# Motor_Driver_v4.net
KiCad netlist of a schematic drawn in EAGLE
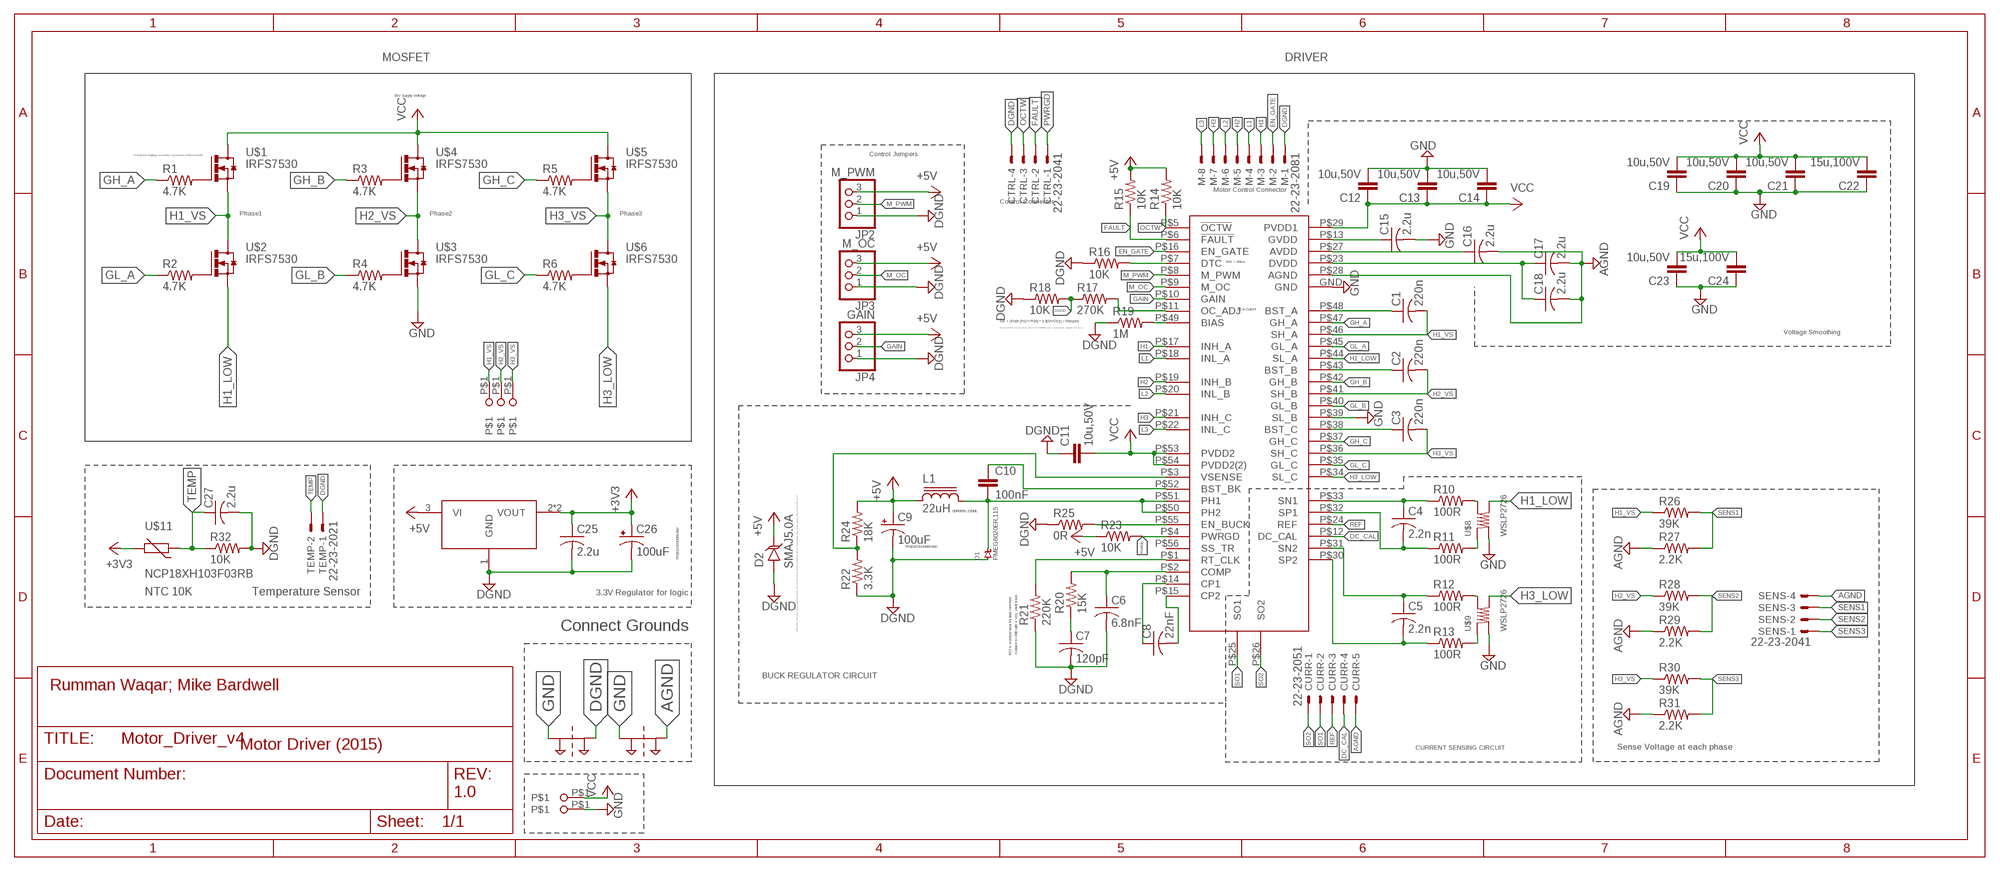
[diagram p0: schematic, sheet 1]

(export (version "E")
  (design (tool "Eeschema 10.0.6"))
  (components
    (comp (ref "C1")
      (value "220n")
      (footprint "eagle-import:C0805")
      (libsource (lib "eagle-import") (part "C-USC0805"))
    )
    (comp (ref "C2")
      (value "220n")
      (footprint "eagle-import:C0805")
      (libsource (lib "eagle-import") (part "C-USC0805"))
    )
    (comp (ref "C3")
      (value "220n")
      (footprint "eagle-import:C0805")
      (libsource (lib "eagle-import") (part "C-USC0805"))
    )
    (comp (ref "C4")
      (value "2.2n")
      (footprint "eagle-import:C0603")
      (libsource (lib "eagle-import") (part "C-USC0603"))
    )
    (comp (ref "C5")
      (value "2.2n")
      (footprint "eagle-import:C0603")
      (libsource (lib "eagle-import") (part "C-USC0603"))
    )
    (comp (ref "C6")
      (value "6.8nF")
      (footprint "eagle-import:C0603")
      (libsource (lib "eagle-import") (part "C-USC0603"))
    )
    (comp (ref "C7")
      (value "120pF")
      (footprint "eagle-import:C0603")
      (libsource (lib "eagle-import") (part "C-USC0603"))
    )
    (comp (ref "C8")
      (value "22nF")
      (footprint "eagle-import:C0603")
      (libsource (lib "eagle-import") (part "C-USC0603"))
    )
    (comp (ref "C9")
      (value "100uF")
      (footprint "eagle-import:EIA3528-KIT")
      (libsource (lib "eagle-import") (part "CAP_POL3528-KIT"))
    )
    (comp (ref "C10")
      (value "100nF")
      (footprint "eagle-import:0805")
      (libsource (lib "eagle-import") (part "CAP0805"))
    )
    (comp (ref "C11")
      (value "10u,50V")
      (footprint "eagle-import:1206")
      (libsource (lib "eagle-import") (part "CAP1206"))
    )
    (comp (ref "C12")
      (value "10u,50V")
      (footprint "eagle-import:1206")
      (libsource (lib "eagle-import") (part "CAP1206"))
    )
    (comp (ref "C13")
      (value "10u,50V")
      (footprint "eagle-import:1206")
      (libsource (lib "eagle-import") (part "CAP1206"))
    )
    (comp (ref "C14")
      (value "10u,50V")
      (footprint "eagle-import:1206")
      (libsource (lib "eagle-import") (part "CAP1206"))
    )
    (comp (ref "C15")
      (value "2.2u")
      (footprint "eagle-import:C0805")
      (libsource (lib "eagle-import") (part "C-USC0805"))
    )
    (comp (ref "C16")
      (value "2.2u")
      (footprint "eagle-import:C0805")
      (libsource (lib "eagle-import") (part "C-USC0805"))
    )
    (comp (ref "C17")
      (value "2.2u")
      (footprint "eagle-import:C0805")
      (libsource (lib "eagle-import") (part "C-USC0805"))
    )
    (comp (ref "C18")
      (value "2.2u")
      (footprint "eagle-import:C0805")
      (libsource (lib "eagle-import") (part "C-USC0805"))
    )
    (comp (ref "C19")
      (value "10u,50V")
      (footprint "eagle-import:1206")
      (libsource (lib "eagle-import") (part "CAP1206"))
    )
    (comp (ref "C20")
      (value "10u,50V")
      (footprint "eagle-import:1206")
      (libsource (lib "eagle-import") (part "CAP1206"))
    )
    (comp (ref "C21")
      (value "10u,50V")
      (footprint "eagle-import:1206")
      (libsource (lib "eagle-import") (part "CAP1206"))
    )
    (comp (ref "C22")
      (value "15u,100V")
      (footprint "eagle-import:C2220K")
      (libsource (lib "eagle-import") (part "C-EUC2220K"))
    )
    (comp (ref "C23")
      (value "10u,50V")
      (footprint "eagle-import:1206")
      (libsource (lib "eagle-import") (part "CAP1206"))
    )
    (comp (ref "C24")
      (value "15u,100V")
      (footprint "eagle-import:C2220K")
      (libsource (lib "eagle-import") (part "C-EUC2220K"))
    )
    (comp (ref "C25")
      (value "2.2u")
      (footprint "eagle-import:C0805")
      (libsource (lib "eagle-import") (part "C-USC0805"))
    )
    (comp (ref "C26")
      (value "100uF")
      (footprint "eagle-import:EIA3528-KIT")
      (libsource (lib "eagle-import") (part "CAP_POL3528-KIT"))
    )
    (comp (ref "C27")
      (value "2.2u")
      (footprint "eagle-import:C0805")
      (libsource (lib "eagle-import") (part "C-USC0805"))
    )
    (comp (ref "CTRL")
      (value "22-23-2041")
      (footprint "eagle-import:22-23-2041")
      (fields (field (name "MF") "MOLEX"))
      (libsource (lib "eagle-import") (part "22-23-2041"))
    )
    (comp (ref "CURR")
      (value "22-23-2051")
      (footprint "eagle-import:22-23-2051")
      (fields (field (name "MF") "MOLEX"))
      (libsource (lib "eagle-import") (part "22-23-2051"))
    )
    (comp (ref "D1")
      (value "PMEG6020ER,115")
      (footprint "eagle-import:SOD123W")
      (libsource (lib "eagle-import") (part "DIODE[SCHOTKY]-SOD123W"))
    )
    (comp (ref "D2")
      (value "SMAJ5.0A")
      (footprint "eagle-import:SMA-DIODE")
      (libsource (lib "eagle-import") (part "TVSSMA"))
    )
    (comp (ref "JP2")
      (value "M_PWM")
      (footprint "eagle-import:1X03")
      (libsource (lib "eagle-import") (part "PINHD-1X3"))
    )
    (comp (ref "JP3")
      (value "M_OC")
      (footprint "eagle-import:1X03")
      (libsource (lib "eagle-import") (part "PINHD-1X3"))
    )
    (comp (ref "JP4")
      (value "GAIN")
      (footprint "eagle-import:1X03")
      (libsource (lib "eagle-import") (part "PINHD-1X3"))
    )
    (comp (ref "L1")
      (value "22uH")
      (footprint "eagle-import:SDR0805")
      (libsource (lib "eagle-import") (part "SDR0805"))
    )
    (comp (ref "M")
      (value "22-23-2081")
      (footprint "eagle-import:22-23-2081")
      (fields (field (name "MF") "MOLEX"))
      (libsource (lib "eagle-import") (part "22-23-2081"))
    )
    (comp (ref "PT1")
      (value "2PT_GND_TIE")
      (footprint "eagle-import:2PT_GND_TIE")
      (libsource (lib "eagle-import") (part "2PT_GND_TIE"))
    )
    (comp (ref "PT2")
      (value "2PT_GND_TIE")
      (footprint "eagle-import:2PT_GND_TIE")
      (libsource (lib "eagle-import") (part "2PT_GND_TIE"))
    )
    (comp (ref "R1")
      (value "4.7K")
      (footprint "eagle-import:R0603")
      (libsource (lib "eagle-import") (part "R-US_R0603"))
    )
    (comp (ref "R2")
      (value "4.7K")
      (footprint "eagle-import:R0603")
      (libsource (lib "eagle-import") (part "R-US_R0603"))
    )
    (comp (ref "R3")
      (value "4.7K")
      (footprint "eagle-import:R0603")
      (libsource (lib "eagle-import") (part "R-US_R0603"))
    )
    (comp (ref "R4")
      (value "4.7K")
      (footprint "eagle-import:R0603")
      (libsource (lib "eagle-import") (part "R-US_R0603"))
    )
    (comp (ref "R5")
      (value "4.7K")
      (footprint "eagle-import:R0603")
      (libsource (lib "eagle-import") (part "R-US_R0603"))
    )
    (comp (ref "R6")
      (value "4.7K")
      (footprint "eagle-import:R0603")
      (libsource (lib "eagle-import") (part "R-US_R0603"))
    )
    (comp (ref "R10")
      (value "100R")
      (footprint "eagle-import:R0603")
      (libsource (lib "eagle-import") (part "R-US_R0603"))
    )
    (comp (ref "R11")
      (value "100R")
      (footprint "eagle-import:R0603")
      (libsource (lib "eagle-import") (part "R-US_R0603"))
    )
    (comp (ref "R12")
      (value "100R")
      (footprint "eagle-import:R0603")
      (libsource (lib "eagle-import") (part "R-US_R0603"))
    )
    (comp (ref "R13")
      (value "100R")
      (footprint "eagle-import:R0603")
      (libsource (lib "eagle-import") (part "R-US_R0603"))
    )
    (comp (ref "R14")
      (value "10K")
      (footprint "eagle-import:R0603")
      (libsource (lib "eagle-import") (part "R-US_R0603"))
    )
    (comp (ref "R15")
      (value "10K")
      (footprint "eagle-import:R0603")
      (libsource (lib "eagle-import") (part "R-US_R0603"))
    )
    (comp (ref "R16")
      (value "10K")
      (footprint "eagle-import:R0603")
      (libsource (lib "eagle-import") (part "R-US_R0603"))
    )
    (comp (ref "R17")
      (value "270K")
      (footprint "eagle-import:R0603")
      (libsource (lib "eagle-import") (part "R-US_R0603"))
    )
    (comp (ref "R18")
      (value "10K")
      (footprint "eagle-import:R0603")
      (libsource (lib "eagle-import") (part "R-US_R0603"))
    )
    (comp (ref "R19")
      (value "1M")
      (footprint "eagle-import:R0603")
      (libsource (lib "eagle-import") (part "R-US_R0603"))
    )
    (comp (ref "R20")
      (value "15K")
      (footprint "eagle-import:R0603")
      (libsource (lib "eagle-import") (part "R-US_R0603"))
    )
    (comp (ref "R21")
      (value "220K")
      (footprint "eagle-import:R0603")
      (libsource (lib "eagle-import") (part "R-US_R0603"))
    )
    (comp (ref "R22")
      (value "3.3K")
      (footprint "eagle-import:R0603")
      (libsource (lib "eagle-import") (part "R-US_R0603"))
    )
    (comp (ref "R23")
      (value "10K")
      (footprint "eagle-import:R0603")
      (libsource (lib "eagle-import") (part "R-US_R0603"))
    )
    (comp (ref "R24")
      (value "18K")
      (footprint "eagle-import:R0603")
      (libsource (lib "eagle-import") (part "R-US_R0603"))
    )
    (comp (ref "R25")
      (value "0R")
      (footprint "eagle-import:R0603")
      (libsource (lib "eagle-import") (part "R-US_R0603"))
    )
    (comp (ref "R26")
      (value "39K")
      (footprint "eagle-import:R0805")
      (libsource (lib "eagle-import") (part "R-US_R0805"))
    )
    (comp (ref "R27")
      (value "2.2K")
      (footprint "eagle-import:R0805")
      (libsource (lib "eagle-import") (part "R-US_R0805"))
    )
    (comp (ref "R28")
      (value "39K")
      (footprint "eagle-import:R0805")
      (libsource (lib "eagle-import") (part "R-US_R0805"))
    )
    (comp (ref "R29")
      (value "2.2K")
      (footprint "eagle-import:R0805")
      (libsource (lib "eagle-import") (part "R-US_R0805"))
    )
    (comp (ref "R30")
      (value "39K")
      (footprint "eagle-import:R0805")
      (libsource (lib "eagle-import") (part "R-US_R0805"))
    )
    (comp (ref "R31")
      (value "2.2K")
      (footprint "eagle-import:R0805")
      (libsource (lib "eagle-import") (part "R-US_R0805"))
    )
    (comp (ref "R32")
      (value "10K")
      (footprint "eagle-import:M0805")
      (libsource (lib "eagle-import") (part "R-US_M0805"))
    )
    (comp (ref "SENS")
      (value "22-23-2041")
      (footprint "eagle-import:22-23-2041")
      (fields (field (name "MF") "MOLEX"))
      (libsource (lib "eagle-import") (part "22-23-2041"))
    )
    (comp (ref "TEMP")
      (value "22-23-2021")
      (footprint "eagle-import:22-23-2021")
      (fields (field (name "MF") "MOLEX"))
      (libsource (lib "eagle-import") (part "22-23-2021"))
    )
    (comp (ref "U$1")
      (value "IRFS7530")
      (footprint "eagle-import:IRF7530_HEATSINK")
      (libsource (lib "eagle-import") (part "IRFS7530_HEATSINK"))
    )
    (comp (ref "U$2")
      (value "IRFS7530")
      (footprint "eagle-import:IRF7530_HEATSINK")
      (libsource (lib "eagle-import") (part "IRFS7530_HEATSINK"))
    )
    (comp (ref "U$3")
      (value "IRFS7530")
      (footprint "eagle-import:IRF7530_HEATSINK")
      (libsource (lib "eagle-import") (part "IRFS7530_HEATSINK"))
    )
    (comp (ref "U$4")
      (value "IRFS7530")
      (footprint "eagle-import:IRF7530_HEATSINK")
      (libsource (lib "eagle-import") (part "IRFS7530_HEATSINK"))
    )
    (comp (ref "U$5")
      (value "IRFS7530")
      (footprint "eagle-import:IRF7530_HEATSINK")
      (libsource (lib "eagle-import") (part "IRFS7530_HEATSINK"))
    )
    (comp (ref "U$6")
      (value "IRFS7530")
      (footprint "eagle-import:IRF7530_HEATSINK")
      (libsource (lib "eagle-import") (part "IRFS7530_HEATSINK"))
    )
    (comp (ref "U$7")
      (value "DRV8302")
      (footprint "eagle-import:DRV8302")
      (libsource (lib "eagle-import") (part "DRV8302"))
    )
    (comp (ref "U$8")
      (value "WSLP2726")
      (footprint "eagle-import:WSLP2726")
      (libsource (lib "eagle-import") (part "WSLP2726"))
    )
    (comp (ref "U$9")
      (value "WSLP2726")
      (footprint "eagle-import:WSLP2726")
      (libsource (lib "eagle-import") (part "WSLP2726"))
    )
    (comp (ref "U$10")
      (value "TC2117")
      (footprint "eagle-import:SOT223")
      (libsource (lib "eagle-import") (part "TC2117"))
    )
    (comp (ref "U$11")
      (value "NCP18XH103F03RB")
      (footprint "eagle-import:R0603")
      (libsource (lib "eagle-import") (part "NCP18XH103F03RB"))
    )
    (comp (ref "U$12")
      (value "1CONN_SOLDER")
      (footprint "eagle-import:1CONN_PAD")
      (libsource (lib "eagle-import") (part "1CONN_SOLDER"))
    )
    (comp (ref "U$13")
      (value "1CONN_SOLDER")
      (footprint "eagle-import:1CONN_PAD")
      (libsource (lib "eagle-import") (part "1CONN_SOLDER"))
    )
    (comp (ref "U$14")
      (value "1CONN_SOLDER")
      (footprint "eagle-import:1CONN_PAD")
      (libsource (lib "eagle-import") (part "1CONN_SOLDER"))
    )
    (comp (ref "U$15")
      (value "1CONN_SOLDER")
      (footprint "eagle-import:1CONN_PAD")
      (libsource (lib "eagle-import") (part "1CONN_SOLDER"))
    )
    (comp (ref "U$16")
      (value "1CONN_SOLDER")
      (footprint "eagle-import:1CONN_PAD")
      (libsource (lib "eagle-import") (part "1CONN_SOLDER"))
    )
  )
  (nets
    (net (code "1") (name "+3V3") (class "Default")
      (node (ref "C25") (pin "1") (pinfunction "1_1") (pintype "passive"))
      (node (ref "C26") (pin "A") (pinfunction "+_A") (pintype "passive"))
      (node (ref "U$10") (pin "2") (pinfunction "VOUT_2") (pintype "bidirectional"))
      (node (ref "U$10") (pin "4") (pinfunction "VOUT_4") (pintype "bidirectional"))
      (node (ref "U$11") (pin "2") (pinfunction "2_2") (pintype "passive"))
    )
    (net (code "2") (name "+5V") (class "Default")
      (node (ref "C9") (pin "A") (pinfunction "+_A") (pintype "passive"))
      (node (ref "D2") (pin "C") (pinfunction "C_C") (pintype "passive"))
      (node (ref "JP2") (pin "3") (pinfunction "3_3") (pintype "passive"))
      (node (ref "JP3") (pin "3") (pinfunction "3_3") (pintype "passive"))
      (node (ref "JP4") (pin "3") (pinfunction "3_3") (pintype "passive"))
      (node (ref "L1") (pin "1") (pinfunction "1_1") (pintype "passive"))
      (node (ref "R14") (pin "2") (pinfunction "2_2") (pintype "passive"))
      (node (ref "R15") (pin "2") (pinfunction "2_2") (pintype "passive"))
      (node (ref "R23") (pin "1") (pinfunction "1_1") (pintype "passive"))
      (node (ref "R24") (pin "2") (pinfunction "2_2") (pintype "passive"))
      (node (ref "U$10") (pin "3") (pinfunction "VI_3") (pintype "bidirectional"))
    )
    (net (code "3") (name "AGND") (class "Default")
      (node (ref "C16") (pin "2") (pinfunction "2_2") (pintype "passive"))
      (node (ref "C17") (pin "2") (pinfunction "2_2") (pintype "passive"))
      (node (ref "C18") (pin "2") (pinfunction "2_2") (pintype "passive"))
      (node (ref "CURR") (pin "5") (pinfunction "S_5") (pintype "passive"))
      (node (ref "PT2") (pin "P$2") (pinfunction "P$2_P$2") (pintype "bidirectional"))
      (node (ref "R27") (pin "1") (pinfunction "1_1") (pintype "passive"))
      (node (ref "R29") (pin "1") (pinfunction "1_1") (pintype "passive"))
      (node (ref "R31") (pin "1") (pinfunction "1_1") (pintype "passive"))
      (node (ref "SENS") (pin "4") (pinfunction "S_4") (pintype "passive"))
      (node (ref "U$7") (pin "P$28") (pinfunction "AGND_P$28") (pintype "bidirectional"))
    )
    (net (code "4") (name "DC_CAL") (class "Default")
      (node (ref "CURR") (pin "4") (pinfunction "S_4") (pintype "passive"))
      (node (ref "U$7") (pin "P$12") (pinfunction "DC_CAL_P$12") (pintype "bidirectional"))
    )
    (net (code "5") (name "DGND") (class "Default")
      (node (ref "C11") (pin "1") (pinfunction "1_1") (pintype "passive"))
      (node (ref "C25") (pin "2") (pinfunction "2_2") (pintype "passive"))
      (node (ref "C26") (pin "C") (pinfunction "-_C") (pintype "passive"))
      (node (ref "C27") (pin "2") (pinfunction "2_2") (pintype "passive"))
      (node (ref "C6") (pin "2") (pinfunction "2_2") (pintype "passive"))
      (node (ref "C7") (pin "2") (pinfunction "2_2") (pintype "passive"))
      (node (ref "C9") (pin "C") (pinfunction "-_C") (pintype "passive"))
      (node (ref "CTRL") (pin "4") (pinfunction "S_4") (pintype "passive"))
      (node (ref "D1") (pin "P$1") (pinfunction "1_P$1") (pintype "bidirectional"))
      (node (ref "D2") (pin "A") (pinfunction "A_A") (pintype "passive"))
      (node (ref "JP2") (pin "1") (pinfunction "1_1") (pintype "passive"))
      (node (ref "JP3") (pin "1") (pinfunction "1_1") (pintype "passive"))
      (node (ref "JP4") (pin "1") (pinfunction "1_1") (pintype "passive"))
      (node (ref "M") (pin "1") (pinfunction "S_1") (pintype "passive"))
      (node (ref "PT1") (pin "P$2") (pinfunction "P$2_P$2") (pintype "bidirectional"))
      (node (ref "R16") (pin "1") (pinfunction "1_1") (pintype "passive"))
      (node (ref "R18") (pin "1") (pinfunction "1_1") (pintype "passive"))
      (node (ref "R19") (pin "1") (pinfunction "1_1") (pintype "passive"))
      (node (ref "R21") (pin "1") (pinfunction "1_1") (pintype "passive"))
      (node (ref "R22") (pin "1") (pinfunction "1_1") (pintype "passive"))
      (node (ref "R25") (pin "1") (pinfunction "1_1") (pintype "passive"))
      (node (ref "R32") (pin "2") (pinfunction "2_2") (pintype "passive"))
      (node (ref "TEMP") (pin "1") (pinfunction "S_1") (pintype "passive"))
      (node (ref "U$10") (pin "1") (pinfunction "GND_1") (pintype "bidirectional"))
    )
    (net (code "6") (name "DVDD") (class "Default")
      (node (ref "R17") (pin "1") (pinfunction "1_1") (pintype "passive"))
      (node (ref "R18") (pin "2") (pinfunction "2_2") (pintype "passive"))
    )
    (net (code "7") (name "EN_GATE") (class "Default")
      (node (ref "M") (pin "2") (pinfunction "S_2") (pintype "passive"))
      (node (ref "U$7") (pin "P$16") (pinfunction "EN_GATE_P$16") (pintype "bidirectional"))
    )
    (net (code "8") (name "FAULT") (class "Default")
      (node (ref "CTRL") (pin "2") (pinfunction "S_2") (pintype "passive"))
      (node (ref "R15") (pin "1") (pinfunction "1_1") (pintype "passive"))
      (node (ref "U$7") (pin "P$6") (pinfunction "~{FAULT}_P$6") (pintype "bidirectional"))
    )
    (net (code "9") (name "GAIN") (class "Default")
      (node (ref "JP4") (pin "2") (pinfunction "2_2") (pintype "passive"))
      (node (ref "U$7") (pin "P$10") (pinfunction "GAIN_P$10") (pintype "bidirectional"))
    )
    (net (code "10") (name "GH_A") (class "Default")
      (node (ref "R1") (pin "1") (pinfunction "1_1") (pintype "passive"))
      (node (ref "U$7") (pin "P$47") (pinfunction "GH_A_P$47") (pintype "bidirectional"))
    )
    (net (code "11") (name "GH_B") (class "Default")
      (node (ref "R3") (pin "1") (pinfunction "1_1") (pintype "passive"))
      (node (ref "U$7") (pin "P$42") (pinfunction "GH_B_P$42") (pintype "bidirectional"))
    )
    (net (code "12") (name "GH_C") (class "Default")
      (node (ref "R5") (pin "1") (pinfunction "1_1") (pintype "passive"))
      (node (ref "U$7") (pin "P$37") (pinfunction "GH_C_P$37") (pintype "bidirectional"))
    )
    (net (code "13") (name "GL_A") (class "Default")
      (node (ref "R2") (pin "1") (pinfunction "1_1") (pintype "passive"))
      (node (ref "U$7") (pin "P$45") (pinfunction "GL_A_P$45") (pintype "bidirectional"))
    )
    (net (code "14") (name "GL_B") (class "Default")
      (node (ref "R4") (pin "1") (pinfunction "1_1") (pintype "passive"))
      (node (ref "U$7") (pin "P$40") (pinfunction "GL_B_P$40") (pintype "bidirectional"))
    )
    (net (code "15") (name "GL_C") (class "Default")
      (node (ref "R6") (pin "1") (pinfunction "1_1") (pintype "passive"))
      (node (ref "U$7") (pin "P$35") (pinfunction "GL_C_P$35") (pintype "bidirectional"))
    )
    (net (code "16") (name "GND") (class "Default")
      (node (ref "C12") (pin "2") (pinfunction "2_2") (pintype "passive"))
      (node (ref "C13") (pin "2") (pinfunction "2_2") (pintype "passive"))
      (node (ref "C14") (pin "2") (pinfunction "2_2") (pintype "passive"))
      (node (ref "C15") (pin "2") (pinfunction "2_2") (pintype "passive"))
      (node (ref "C19") (pin "1") (pinfunction "1_1") (pintype "passive"))
      (node (ref "C20") (pin "1") (pinfunction "1_1") (pintype "passive"))
      (node (ref "C21") (pin "1") (pinfunction "1_1") (pintype "passive"))
      (node (ref "C22") (pin "1") (pinfunction "1_1") (pintype "passive"))
      (node (ref "C23") (pin "1") (pinfunction "1_1") (pintype "passive"))
      (node (ref "C24") (pin "1") (pinfunction "1_1") (pintype "passive"))
      (node (ref "PT1") (pin "P$1") (pinfunction "P$1_P$1") (pintype "bidirectional"))
      (node (ref "PT2") (pin "P$1") (pinfunction "P$1_P$1") (pintype "bidirectional"))
      (node (ref "U$16") (pin "P$1") (pinfunction "P$1_P$1") (pintype "bidirectional"))
      (node (ref "U$3") (pin "S1") (pinfunction "S_S1") (pintype "passive"))
      (node (ref "U$3") (pin "S2") (pinfunction "S_S2") (pintype "passive"))
      (node (ref "U$3") (pin "S3") (pinfunction "S_S3") (pintype "passive"))
      (node (ref "U$3") (pin "S4") (pinfunction "S_S4") (pintype "passive"))
      (node (ref "U$3") (pin "S5") (pinfunction "S_S5") (pintype "passive"))
      (node (ref "U$7") (pin "GND") (pinfunction "GND_GND") (pintype "bidirectional"))
      (node (ref "U$7") (pin "P$39") (pinfunction "SL_B_P$39") (pintype "bidirectional"))
      (node (ref "U$8") (pin "P$2") (pinfunction "P$2_P$2") (pintype "bidirectional"))
      (node (ref "U$9") (pin "P$2") (pinfunction "P$2_P$2") (pintype "bidirectional"))
    )
    (net (code "17") (name "H1") (class "Default")
      (node (ref "M") (pin "3") (pinfunction "S_3") (pintype "passive"))
      (node (ref "U$7") (pin "P$17") (pinfunction "INH_A_P$17") (pintype "bidirectional"))
    )
    (net (code "18") (name "H1_LOW") (class "Default")
      (node (ref "U$2") (pin "S1") (pinfunction "S_S1") (pintype "passive"))
      (node (ref "U$2") (pin "S2") (pinfunction "S_S2") (pintype "passive"))
      (node (ref "U$2") (pin "S3") (pinfunction "S_S3") (pintype "passive"))
      (node (ref "U$2") (pin "S4") (pinfunction "S_S4") (pintype "passive"))
      (node (ref "U$2") (pin "S5") (pinfunction "S_S5") (pintype "passive"))
      (node (ref "U$7") (pin "P$44") (pinfunction "SL_A_P$44") (pintype "bidirectional"))
      (node (ref "U$8") (pin "P$1") (pinfunction "P$1_P$1") (pintype "bidirectional"))
    )
    (net (code "19") (name "H1_VS") (class "Default")
      (node (ref "C1") (pin "2") (pinfunction "2_2") (pintype "passive"))
      (node (ref "R26") (pin "1") (pinfunction "1_1") (pintype "passive"))
      (node (ref "U$1") (pin "S1") (pinfunction "S_S1") (pintype "passive"))
      (node (ref "U$1") (pin "S2") (pinfunction "S_S2") (pintype "passive"))
      (node (ref "U$1") (pin "S3") (pinfunction "S_S3") (pintype "passive"))
      (node (ref "U$1") (pin "S4") (pinfunction "S_S4") (pintype "passive"))
      (node (ref "U$1") (pin "S5") (pinfunction "S_S5") (pintype "passive"))
      (node (ref "U$14") (pin "P$1") (pinfunction "P$1_P$1") (pintype "bidirectional"))
      (node (ref "U$2") (pin "D1") (pinfunction "D_D1") (pintype "passive"))
      (node (ref "U$7") (pin "P$46") (pinfunction "SH_A_P$46") (pintype "bidirectional"))
    )
    (net (code "20") (name "H2") (class "Default")
      (node (ref "M") (pin "5") (pinfunction "S_5") (pintype "passive"))
      (node (ref "U$7") (pin "P$19") (pinfunction "INH_B_P$19") (pintype "bidirectional"))
    )
    (net (code "21") (name "H2_VS") (class "Default")
      (node (ref "C2") (pin "2") (pinfunction "2_2") (pintype "passive"))
      (node (ref "R28") (pin "1") (pinfunction "1_1") (pintype "passive"))
      (node (ref "U$13") (pin "P$1") (pinfunction "P$1_P$1") (pintype "bidirectional"))
      (node (ref "U$3") (pin "D1") (pinfunction "D_D1") (pintype "passive"))
      (node (ref "U$4") (pin "S1") (pinfunction "S_S1") (pintype "passive"))
      (node (ref "U$4") (pin "S2") (pinfunction "S_S2") (pintype "passive"))
      (node (ref "U$4") (pin "S3") (pinfunction "S_S3") (pintype "passive"))
      (node (ref "U$4") (pin "S4") (pinfunction "S_S4") (pintype "passive"))
      (node (ref "U$4") (pin "S5") (pinfunction "S_S5") (pintype "passive"))
      (node (ref "U$7") (pin "P$41") (pinfunction "SH_B_P$41") (pintype "bidirectional"))
    )
    (net (code "22") (name "H3") (class "Default")
      (node (ref "M") (pin "7") (pinfunction "S_7") (pintype "passive"))
      (node (ref "U$7") (pin "P$21") (pinfunction "INH_C_P$21") (pintype "bidirectional"))
    )
    (net (code "23") (name "H3_LOW") (class "Default")
      (node (ref "U$6") (pin "S1") (pinfunction "S_S1") (pintype "passive"))
      (node (ref "U$6") (pin "S2") (pinfunction "S_S2") (pintype "passive"))
      (node (ref "U$6") (pin "S3") (pinfunction "S_S3") (pintype "passive"))
      (node (ref "U$6") (pin "S4") (pinfunction "S_S4") (pintype "passive"))
      (node (ref "U$6") (pin "S5") (pinfunction "S_S5") (pintype "passive"))
      (node (ref "U$7") (pin "P$34") (pinfunction "SL_C_P$34") (pintype "bidirectional"))
      (node (ref "U$9") (pin "P$1") (pinfunction "P$1_P$1") (pintype "bidirectional"))
    )
    (net (code "24") (name "H3_VS") (class "Default")
      (node (ref "C3") (pin "2") (pinfunction "2_2") (pintype "passive"))
      (node (ref "R30") (pin "1") (pinfunction "1_1") (pintype "passive"))
      (node (ref "U$12") (pin "P$1") (pinfunction "P$1_P$1") (pintype "bidirectional"))
      (node (ref "U$5") (pin "S1") (pinfunction "S_S1") (pintype "passive"))
      (node (ref "U$5") (pin "S2") (pinfunction "S_S2") (pintype "passive"))
      (node (ref "U$5") (pin "S3") (pinfunction "S_S3") (pintype "passive"))
      (node (ref "U$5") (pin "S4") (pinfunction "S_S4") (pintype "passive"))
      (node (ref "U$5") (pin "S5") (pinfunction "S_S5") (pintype "passive"))
      (node (ref "U$6") (pin "D1") (pinfunction "D_D1") (pintype "passive"))
      (node (ref "U$7") (pin "P$36") (pinfunction "SH_C_P$36") (pintype "bidirectional"))
    )
    (net (code "25") (name "L1") (class "Default")
      (node (ref "M") (pin "4") (pinfunction "S_4") (pintype "passive"))
      (node (ref "U$7") (pin "P$18") (pinfunction "INL_A_P$18") (pintype "bidirectional"))
    )
    (net (code "26") (name "L2") (class "Default")
      (node (ref "M") (pin "6") (pinfunction "S_6") (pintype "passive"))
      (node (ref "U$7") (pin "P$20") (pinfunction "INL_B_P$20") (pintype "bidirectional"))
    )
    (net (code "27") (name "L3") (class "Default")
      (node (ref "M") (pin "8") (pinfunction "S_8") (pintype "passive"))
      (node (ref "U$7") (pin "P$22") (pinfunction "INL_C_P$22") (pintype "bidirectional"))
    )
    (net (code "28") (name "M_OC") (class "Default")
      (node (ref "JP3") (pin "2") (pinfunction "2_2") (pintype "passive"))
      (node (ref "U$7") (pin "P$9") (pinfunction "M_OC_P$9") (pintype "bidirectional"))
    )
    (net (code "29") (name "M_PWM") (class "Default")
      (node (ref "JP2") (pin "2") (pinfunction "2_2") (pintype "passive"))
      (node (ref "U$7") (pin "P$8") (pinfunction "M_PWM_P$8") (pintype "bidirectional"))
    )
    (net (code "30") (name "Net-(C7-Pad1)") (class "Default")
      (node (ref "C7") (pin "1") (pinfunction "1_1") (pintype "passive"))
      (node (ref "R20") (pin "1") (pinfunction "1_1") (pintype "passive"))
    )
    (net (code "31") (name "Net-(D1-2)") (class "Default")
      (node (ref "C10") (pin "2") (pinfunction "2_2") (pintype "passive"))
      (node (ref "D1") (pin "P$2") (pinfunction "2_P$2") (pintype "bidirectional"))
      (node (ref "L1") (pin "2") (pinfunction "2_2") (pintype "passive"))
      (node (ref "U$7") (pin "P$50") (pinfunction "PH2_P$50") (pintype "bidirectional"))
      (node (ref "U$7") (pin "P$51") (pinfunction "PH1_P$51") (pintype "bidirectional"))
    )
    (net (code "32") (name "Net-(R10-Pad2)") (class "Default")
      (node (ref "R10") (pin "2") (pinfunction "2_2") (pintype "passive"))
      (node (ref "U$8") (pin "P$3") (pinfunction "P$3_P$3") (pintype "bidirectional"))
    )
    (net (code "33") (name "Net-(R11-Pad2)") (class "Default")
      (node (ref "R11") (pin "2") (pinfunction "2_2") (pintype "passive"))
      (node (ref "U$8") (pin "P$4") (pinfunction "P$4_P$4") (pintype "bidirectional"))
    )
    (net (code "34") (name "Net-(R12-Pad2)") (class "Default")
      (node (ref "R12") (pin "2") (pinfunction "2_2") (pintype "passive"))
      (node (ref "U$9") (pin "P$3") (pinfunction "P$3_P$3") (pintype "bidirectional"))
    )
    (net (code "35") (name "Net-(R13-Pad2)") (class "Default")
      (node (ref "R13") (pin "2") (pinfunction "2_2") (pintype "passive"))
      (node (ref "U$9") (pin "P$4") (pinfunction "P$4_P$4") (pintype "bidirectional"))
    )
    (net (code "36") (name "Net-(U$1-G)") (class "Default")
      (node (ref "R1") (pin "2") (pinfunction "2_2") (pintype "passive"))
      (node (ref "U$1") (pin "G1") (pinfunction "G_G1") (pintype "passive"))
    )
    (net (code "37") (name "Net-(U$2-G)") (class "Default")
      (node (ref "R2") (pin "2") (pinfunction "2_2") (pintype "passive"))
      (node (ref "U$2") (pin "G1") (pinfunction "G_G1") (pintype "passive"))
    )
    (net (code "38") (name "Net-(U$3-G)") (class "Default")
      (node (ref "R4") (pin "2") (pinfunction "2_2") (pintype "passive"))
      (node (ref "U$3") (pin "G1") (pinfunction "G_G1") (pintype "passive"))
    )
    (net (code "39") (name "Net-(U$4-G)") (class "Default")
      (node (ref "R3") (pin "2") (pinfunction "2_2") (pintype "passive"))
      (node (ref "U$4") (pin "G1") (pinfunction "G_G1") (pintype "passive"))
    )
    (net (code "40") (name "Net-(U$5-G)") (class "Default")
      (node (ref "R5") (pin "2") (pinfunction "2_2") (pintype "passive"))
      (node (ref "U$5") (pin "G1") (pinfunction "G_G1") (pintype "passive"))
    )
    (net (code "41") (name "Net-(U$6-G)") (class "Default")
      (node (ref "R6") (pin "2") (pinfunction "2_2") (pintype "passive"))
      (node (ref "U$6") (pin "G1") (pinfunction "G_G1") (pintype "passive"))
    )
    (net (code "42") (name "Net-(U$7-AVDD)") (class "Default")
      (node (ref "C16") (pin "1") (pinfunction "1_1") (pintype "passive"))
      (node (ref "U$7") (pin "P$27") (pinfunction "AVDD_P$27") (pintype "bidirectional"))
    )
    (net (code "43") (name "Net-(U$7-BIAS)") (class "Default")
      (node (ref "R19") (pin "2") (pinfunction "2_2") (pintype "passive"))
      (node (ref "U$7") (pin "P$49") (pinfunction "BIAS_P$49") (pintype "bidirectional"))
    )
    (net (code "44") (name "Net-(U$7-BST_A)") (class "Default")
      (node (ref "C1") (pin "1") (pinfunction "1_1") (pintype "passive"))
      (node (ref "U$7") (pin "P$48") (pinfunction "BST_A_P$48") (pintype "bidirectional"))
    )
    (net (code "45") (name "Net-(U$7-BST_B)") (class "Default")
      (node (ref "C2") (pin "1") (pinfunction "1_1") (pintype "passive"))
      (node (ref "U$7") (pin "P$43") (pinfunction "BST_B_P$43") (pintype "bidirectional"))
    )
    (net (code "46") (name "Net-(U$7-BST_BK)") (class "Default")
      (node (ref "C10") (pin "1") (pinfunction "1_1") (pintype "passive"))
      (node (ref "U$7") (pin "P$52") (pinfunction "BST_BK_P$52") (pintype "bidirectional"))
    )
    (net (code "47") (name "Net-(U$7-BST_C)") (class "Default")
      (node (ref "C3") (pin "1") (pinfunction "1_1") (pintype "passive"))
      (node (ref "U$7") (pin "P$38") (pinfunction "BST_C_P$38") (pintype "bidirectional"))
    )
    (net (code "48") (name "Net-(U$7-COMP)") (class "Default")
      (node (ref "C6") (pin "1") (pinfunction "1_1") (pintype "passive"))
      (node (ref "R20") (pin "2") (pinfunction "2_2") (pintype "passive"))
      (node (ref "U$7") (pin "P$2") (pinfunction "COMP_P$2") (pintype "bidirectional"))
    )
    (net (code "49") (name "Net-(U$7-CP1)") (class "Default")
      (node (ref "C8") (pin "1") (pinfunction "1_1") (pintype "passive"))
      (node (ref "U$7") (pin "P$14") (pinfunction "CP1_P$14") (pintype "bidirectional"))
    )
    (net (code "50") (name "Net-(U$7-CP2)") (class "Default")
      (node (ref "C8") (pin "2") (pinfunction "2_2") (pintype "passive"))
      (node (ref "U$7") (pin "P$15") (pinfunction "CP2_P$15") (pintype "bidirectional"))
    )
    (net (code "51") (name "Net-(U$7-DTC)") (class "Default")
      (node (ref "R16") (pin "2") (pinfunction "2_2") (pintype "passive"))
      (node (ref "U$7") (pin "P$7") (pinfunction "DTC_P$7") (pintype "bidirectional"))
    )
    (net (code "52") (name "Net-(U$7-DVDD)") (class "Default")
      (node (ref "C17") (pin "1") (pinfunction "1_1") (pintype "passive"))
      (node (ref "C18") (pin "1") (pinfunction "1_1") (pintype "passive"))
      (node (ref "U$7") (pin "P$23") (pinfunction "DVDD_P$23") (pintype "bidirectional"))
    )
    (net (code "53") (name "Net-(U$7-EN_BUCK)") (class "Default")
      (node (ref "R25") (pin "2") (pinfunction "2_2") (pintype "passive"))
      (node (ref "U$7") (pin "P$55") (pinfunction "EN_BUCK_P$55") (pintype "bidirectional"))
    )
    (net (code "54") (name "Net-(U$7-GVDD)") (class "Default")
      (node (ref "C15") (pin "1") (pinfunction "1_1") (pintype "passive"))
      (node (ref "U$7") (pin "P$13") (pinfunction "GVDD_P$13") (pintype "bidirectional"))
    )
    (net (code "55") (name "Net-(U$7-OC_ADJ)") (class "Default")
      (node (ref "R17") (pin "2") (pinfunction "2_2") (pintype "passive"))
      (node (ref "U$7") (pin "P$11") (pinfunction "OC_ADJ_P$11") (pintype "bidirectional"))
    )
    (net (code "56") (name "Net-(U$7-RT_CLK)") (class "Default")
      (node (ref "R21") (pin "2") (pinfunction "2_2") (pintype "passive"))
      (node (ref "U$7") (pin "P$1") (pinfunction "RT_CLK_P$1") (pintype "bidirectional"))
    )
    (net (code "57") (name "Net-(U$7-SN1)") (class "Default")
      (node (ref "C4") (pin "1") (pinfunction "1_1") (pintype "passive"))
      (node (ref "R10") (pin "1") (pinfunction "1_1") (pintype "passive"))
      (node (ref "U$7") (pin "P$33") (pinfunction "SN1_P$33") (pintype "bidirectional"))
    )
    (net (code "58") (name "Net-(U$7-SN2)") (class "Default")
      (node (ref "C5") (pin "1") (pinfunction "1_1") (pintype "passive"))
      (node (ref "R12") (pin "1") (pinfunction "1_1") (pintype "passive"))
      (node (ref "U$7") (pin "P$31") (pinfunction "SN2_P$31") (pintype "bidirectional"))
    )
    (net (code "59") (name "Net-(U$7-SP1)") (class "Default")
      (node (ref "C4") (pin "2") (pinfunction "2_2") (pintype "passive"))
      (node (ref "R11") (pin "1") (pinfunction "1_1") (pintype "passive"))
      (node (ref "U$7") (pin "P$32") (pinfunction "SP1_P$32") (pintype "bidirectional"))
    )
    (net (code "60") (name "Net-(U$7-SP2)") (class "Default")
      (node (ref "C5") (pin "2") (pinfunction "2_2") (pintype "passive"))
      (node (ref "R13") (pin "1") (pinfunction "1_1") (pintype "passive"))
      (node (ref "U$7") (pin "P$30") (pinfunction "SP2_P$30") (pintype "bidirectional"))
    )
    (net (code "61") (name "Net-(U$7-VSENSE)") (class "Default")
      (node (ref "R22") (pin "2") (pinfunction "2_2") (pintype "passive"))
      (node (ref "R24") (pin "1") (pinfunction "1_1") (pintype "passive"))
      (node (ref "U$7") (pin "P$3") (pinfunction "VSENSE_P$3") (pintype "bidirectional"))
    )
    (net (code "62") (name "OCTW") (class "Default")
      (node (ref "CTRL") (pin "3") (pinfunction "S_3") (pintype "passive"))
      (node (ref "R14") (pin "1") (pinfunction "1_1") (pintype "passive"))
      (node (ref "U$7") (pin "P$5") (pinfunction "~{OCTW}_P$5") (pintype "bidirectional"))
    )
    (net (code "63") (name "PWRGD") (class "Default")
      (node (ref "CTRL") (pin "1") (pinfunction "S_1") (pintype "passive"))
      (node (ref "R23") (pin "2") (pinfunction "2_2") (pintype "passive"))
      (node (ref "U$7") (pin "P$4") (pinfunction "PWRGD_P$4") (pintype "bidirectional"))
    )
    (net (code "64") (name "REF") (class "Default")
      (node (ref "CURR") (pin "3") (pinfunction "S_3") (pintype "passive"))
      (node (ref "U$7") (pin "P$24") (pinfunction "REF_P$24") (pintype "bidirectional"))
    )
    (net (code "65") (name "SENS1") (class "Default")
      (node (ref "R26") (pin "2") (pinfunction "2_2") (pintype "passive"))
      (node (ref "R27") (pin "2") (pinfunction "2_2") (pintype "passive"))
      (node (ref "SENS") (pin "3") (pinfunction "S_3") (pintype "passive"))
    )
    (net (code "66") (name "SENS2") (class "Default")
      (node (ref "R28") (pin "2") (pinfunction "2_2") (pintype "passive"))
      (node (ref "R29") (pin "2") (pinfunction "2_2") (pintype "passive"))
      (node (ref "SENS") (pin "2") (pinfunction "S_2") (pintype "passive"))
    )
    (net (code "67") (name "SENS3") (class "Default")
      (node (ref "R30") (pin "2") (pinfunction "2_2") (pintype "passive"))
      (node (ref "R31") (pin "2") (pinfunction "2_2") (pintype "passive"))
      (node (ref "SENS") (pin "1") (pinfunction "S_1") (pintype "passive"))
    )
    (net (code "68") (name "SO1") (class "Default")
      (node (ref "CURR") (pin "2") (pinfunction "S_2") (pintype "passive"))
      (node (ref "U$7") (pin "P$25") (pinfunction "SO1_P$25") (pintype "bidirectional"))
    )
    (net (code "69") (name "SO2") (class "Default")
      (node (ref "CURR") (pin "1") (pinfunction "S_1") (pintype "passive"))
      (node (ref "U$7") (pin "P$26") (pinfunction "SO2_P$26") (pintype "bidirectional"))
    )
    (net (code "70") (name "TEMP") (class "Default")
      (node (ref "C27") (pin "1") (pinfunction "1_1") (pintype "passive"))
      (node (ref "R32") (pin "1") (pinfunction "1_1") (pintype "passive"))
      (node (ref "TEMP") (pin "2") (pinfunction "S_2") (pintype "passive"))
      (node (ref "U$11") (pin "1") (pinfunction "1_1") (pintype "passive"))
    )
    (net (code "71") (name "VCC") (class "Default")
      (node (ref "C11") (pin "2") (pinfunction "2_2") (pintype "passive"))
      (node (ref "C12") (pin "1") (pinfunction "1_1") (pintype "passive"))
      (node (ref "C13") (pin "1") (pinfunction "1_1") (pintype "passive"))
      (node (ref "C14") (pin "1") (pinfunction "1_1") (pintype "passive"))
      (node (ref "C19") (pin "2") (pinfunction "2_2") (pintype "passive"))
      (node (ref "C20") (pin "2") (pinfunction "2_2") (pintype "passive"))
      (node (ref "C21") (pin "2") (pinfunction "2_2") (pintype "passive"))
      (node (ref "C22") (pin "2") (pinfunction "2_2") (pintype "passive"))
      (node (ref "C23") (pin "2") (pinfunction "2_2") (pintype "passive"))
      (node (ref "C24") (pin "2") (pinfunction "2_2") (pintype "passive"))
      (node (ref "U$1") (pin "D1") (pinfunction "D_D1") (pintype "passive"))
      (node (ref "U$15") (pin "P$1") (pinfunction "P$1_P$1") (pintype "bidirectional"))
      (node (ref "U$4") (pin "D1") (pinfunction "D_D1") (pintype "passive"))
      (node (ref "U$5") (pin "D1") (pinfunction "D_D1") (pintype "passive"))
      (node (ref "U$7") (pin "P$29") (pinfunction "PVDD1_P$29") (pintype "bidirectional"))
      (node (ref "U$7") (pin "P$53") (pinfunction "PVDD2_P$53") (pintype "bidirectional"))
      (node (ref "U$7") (pin "P$54") (pinfunction "PVDD2(2)_P$54") (pintype "bidirectional"))
    )
    (net (code "72") (name "unconnected-(U$7-SS_TR-PadP$56)") (class "Default")
      (node (ref "U$7") (pin "P$56") (pinfunction "SS_TR_P$56") (pintype "bidirectional"))
    )
  )
)
